# CD4060BM.net
KiCad netlist of a schematic drawn in Altium Designer
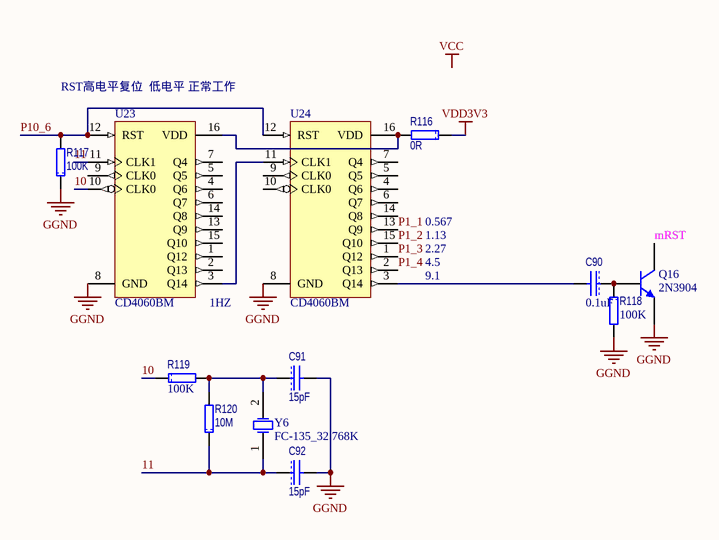
[diagram p0: CD4060BM_硬件定时器.SchDoc]

(export (version "E")
  (design (tool "Eeschema 10.0.6"))
  (components
    (comp (ref "C90")
      (value "0.1uF")
      (footprint "1608[0603]C")
      (description "多层陶瓷电容器MLCC - SMD/SMT 0603 0.1uF 50volts X7R 10%")
      (fields (field (name "MANUFACTURER") "TDK") (field (name "MANUFACTURER PART NUMBER") "C1608X7R1H104K"))
      (libsource (lib "*") (part "CAP"))
    )
    (comp (ref "C91")
      (value "15pF")
      (footprint "1608[0603]")
      (description "Capacitor")
      (fields (field (name "MANUFACTURER") "TDK"))
      (libsource (lib "*") (part "CAP"))
    )
    (comp (ref "C92")
      (value "15pF")
      (footprint "1608[0603]")
      (description "Capacitor")
      (fields (field (name "MANUFACTURER") "TDK"))
      (libsource (lib "*") (part "CAP"))
    )
    (comp (ref "Q16")
      (value "2N3904")
      (footprint "SOT23_N")
      (description "NPN General Purpose Amplifier")
      (fields (field (name "PUBLISHER") "Altium Limited"))
      (libsource (lib "Miscellaneous Devices") (part "2N3904"))
    )
    (comp (ref "R116")
      (value "0R")
      (footprint "1608[0603]R")
      (description "RES")
      (libsource (lib "*") (part "RES"))
    )
    (comp (ref "R117")
      (value "100K")
      (footprint "1608[0603]R")
      (description "RES")
      (libsource (lib "*") (part "RES"))
    )
    (comp (ref "R118")
      (value "100K")
      (footprint "1608[0603]R")
      (description "厚膜电阻器 - SMD 1/10watt 100Kohms 1%")
      (fields
        (field (name "MANUFACTURER") "Vishay / Dale")
        (field (name "MANUFACTURER PART NUMBER") "CRCW0603100KFKEA")
      )
      (libsource (lib "100K 1%") (part "RES"))
    )
    (comp (ref "R119")
      (value "100K")
      (footprint "1608[0603]R")
      (description "厚膜电阻器 - SMD 1/10watt 100Kohms 1%")
      (fields
        (field (name "MANUFACTURER") "Vishay / Dale")
        (field (name "MANUFACTURER PART NUMBER") "CRCW0603100KFKEA")
      )
      (libsource (lib "100K 1%") (part "RES"))
    )
    (comp (ref "R120")
      (value "10M")
      (footprint "1608[0603]R")
      (description "RES")
      (libsource (lib "*") (part "RES"))
    )
    (comp (ref "U23")
      (value "CD4060BM")
      (footprint "SOIC16_N")
      (description "14-Stage Ripple Carry Binary Counter")
      (fields (field (name "PUBLISHER") "Altium Limited"))
      (libsource (lib "FSC Logic Counter") (part "CD4060BCM"))
    )
    (comp (ref "U24")
      (value "CD4060BM")
      (footprint "SOIC16_N")
      (description "14-Stage Ripple Carry Binary Counter")
      (fields (field (name "PUBLISHER") "Altium Limited"))
      (libsource (lib "FSC Logic Counter") (part "CD4060BCM"))
    )
    (comp (ref "Y6")
      (value "FC-135_32.768K")
      (footprint "FC-135")
      (description "Crystal Oscillator")
      (fields (field (name "PUBLISHER") "Altium Limited"))
      (libsource (lib "Miscellaneous Devices") (part "XTAL"))
    )
  )
  (nets
    (net (code "1") (name "/10") (class "Default")
      (node (ref "R119") (pin "1") (pinfunction "1_1") (pintype "passive"))
      (node (ref "U23") (pin "10") (pinfunction "CLK0_10") (pintype "output"))
    )
    (net (code "2") (name "/11") (class "Default")
      (node (ref "C92") (pin "1") (pinfunction "1_1") (pintype "passive"))
      (node (ref "R120") (pin "1") (pinfunction "1_1") (pintype "passive"))
      (node (ref "U23") (pin "11") (pinfunction "CLK1_11") (pintype "input"))
      (node (ref "Y6") (pin "1") (pinfunction "OSC1_1") (pintype "passive"))
    )
    (net (code "3") (name "/P1_1") (class "Default")
      (node (ref "U24") (pin "13") (pinfunction "Q9_13") (pintype "output"))
    )
    (net (code "4") (name "/P1_2") (class "Default")
      (node (ref "U24") (pin "15") (pinfunction "Q10_15") (pintype "output"))
    )
    (net (code "5") (name "/P1_3") (class "Default")
      (node (ref "U24") (pin "1") (pinfunction "Q12_1") (pintype "output"))
    )
    (net (code "6") (name "/P1_4") (class "Default")
      (node (ref "U24") (pin "2") (pinfunction "Q13_2") (pintype "output"))
    )
    (net (code "7") (name "/P10_6") (class "Default")
      (node (ref "R117") (pin "2") (pinfunction "2_2") (pintype "passive"))
      (node (ref "U23") (pin "12") (pinfunction "RST_12") (pintype "input"))
      (node (ref "U24") (pin "12") (pinfunction "RST_12") (pintype "input"))
    )
    (net (code "8") (name "/mRST") (class "Default")
      (node (ref "Q16") (pin "3") (pinfunction "C_3") (pintype "passive"))
    )
    (net (code "9") (name "GGND") (class "Default")
      (node (ref "C91") (pin "2") (pinfunction "2_2") (pintype "passive"))
      (node (ref "C92") (pin "2") (pinfunction "2_2") (pintype "passive"))
      (node (ref "Q16") (pin "1") (pinfunction "E_1") (pintype "passive"))
      (node (ref "R117") (pin "1") (pinfunction "1_1") (pintype "passive"))
      (node (ref "R118") (pin "2") (pinfunction "2_2") (pintype "passive"))
      (node (ref "U23") (pin "8") (pinfunction "GND_8") (pintype "power_in"))
      (node (ref "U24") (pin "8") (pinfunction "GND_8") (pintype "power_in"))
    )
    (net (code "10") (name "Net-(Q16-B)") (class "Default")
      (node (ref "C90") (pin "1") (pinfunction "1_1") (pintype "passive"))
      (node (ref "Q16") (pin "2") (pinfunction "B_2") (pintype "passive"))
      (node (ref "R118") (pin "1") (pinfunction "1_1") (pintype "passive"))
    )
    (net (code "11") (name "Net-(U23-Q14)") (class "Default")
      (node (ref "U23") (pin "3") (pinfunction "Q14_3") (pintype "output"))
      (node (ref "U24") (pin "11") (pinfunction "CLK1_11") (pintype "input"))
    )
    (net (code "12") (name "Net-(U23-VDD)") (class "Default")
      (node (ref "R116") (pin "2") (pinfunction "2_2") (pintype "passive"))
      (node (ref "U23") (pin "16") (pinfunction "VDD_16") (pintype "power_in"))
      (node (ref "U24") (pin "16") (pinfunction "VDD_16") (pintype "power_in"))
    )
    (net (code "13") (name "Net-(U24-Q14)") (class "Default")
      (node (ref "C90") (pin "2") (pinfunction "2_2") (pintype "passive"))
      (node (ref "U24") (pin "3") (pinfunction "Q14_3") (pintype "output"))
    )
    (net (code "14") (name "Net-(Y6-OSC2)") (class "Default")
      (node (ref "C91") (pin "1") (pinfunction "1_1") (pintype "passive"))
      (node (ref "R119") (pin "2") (pinfunction "2_2") (pintype "passive"))
      (node (ref "R120") (pin "2") (pinfunction "2_2") (pintype "passive"))
      (node (ref "Y6") (pin "2") (pinfunction "OSC2_2") (pintype "passive"))
    )
    (net (code "16") (name "VDD3V3") (class "Default")
      (node (ref "R116") (pin "1") (pinfunction "1_1") (pintype "passive"))
    )
    (net (code "17") (name "unconnected-(U23-CLK0-Pad9)") (class "Default")
      (node (ref "U23") (pin "9") (pinfunction "CLK0_9") (pintype "output"))
    )
    (net (code "18") (name "unconnected-(U23-Q4-Pad7)") (class "Default")
      (node (ref "U23") (pin "7") (pinfunction "Q4_7") (pintype "output"))
    )
    (net (code "19") (name "unconnected-(U23-Q5-Pad5)") (class "Default")
      (node (ref "U23") (pin "5") (pinfunction "Q5_5") (pintype "output"))
    )
    (net (code "20") (name "unconnected-(U23-Q6-Pad4)") (class "Default")
      (node (ref "U23") (pin "4") (pinfunction "Q6_4") (pintype "output"))
    )
    (net (code "21") (name "unconnected-(U23-Q7-Pad6)") (class "Default")
      (node (ref "U23") (pin "6") (pinfunction "Q7_6") (pintype "output"))
    )
    (net (code "22") (name "unconnected-(U23-Q8-Pad14)") (class "Default")
      (node (ref "U23") (pin "14") (pinfunction "Q8_14") (pintype "output"))
    )
    (net (code "23") (name "unconnected-(U23-Q9-Pad13)") (class "Default")
      (node (ref "U23") (pin "13") (pinfunction "Q9_13") (pintype "output"))
    )
    (net (code "24") (name "unconnected-(U23-Q10-Pad15)") (class "Default")
      (node (ref "U23") (pin "15") (pinfunction "Q10_15") (pintype "output"))
    )
    (net (code "25") (name "unconnected-(U23-Q12-Pad1)") (class "Default")
      (node (ref "U23") (pin "1") (pinfunction "Q12_1") (pintype "output"))
    )
    (net (code "26") (name "unconnected-(U23-Q13-Pad2)") (class "Default")
      (node (ref "U23") (pin "2") (pinfunction "Q13_2") (pintype "output"))
    )
    (net (code "27") (name "unconnected-(U24-CLK0-Pad9)") (class "Default")
      (node (ref "U24") (pin "9") (pinfunction "CLK0_9") (pintype "output"))
    )
    (net (code "28") (name "unconnected-(U24-CLK0-Pad10)") (class "Default")
      (node (ref "U24") (pin "10") (pinfunction "CLK0_10") (pintype "output"))
    )
    (net (code "29") (name "unconnected-(U24-Q4-Pad7)") (class "Default")
      (node (ref "U24") (pin "7") (pinfunction "Q4_7") (pintype "output"))
    )
    (net (code "30") (name "unconnected-(U24-Q5-Pad5)") (class "Default")
      (node (ref "U24") (pin "5") (pinfunction "Q5_5") (pintype "output"))
    )
    (net (code "31") (name "unconnected-(U24-Q6-Pad4)") (class "Default")
      (node (ref "U24") (pin "4") (pinfunction "Q6_4") (pintype "output"))
    )
    (net (code "32") (name "unconnected-(U24-Q7-Pad6)") (class "Default")
      (node (ref "U24") (pin "6") (pinfunction "Q7_6") (pintype "output"))
    )
    (net (code "33") (name "unconnected-(U24-Q8-Pad14)") (class "Default")
      (node (ref "U24") (pin "14") (pinfunction "Q8_14") (pintype "output"))
    )
  )
)
